# geiger-v2.net
KiCad netlist of a schematic drawn in EAGLE
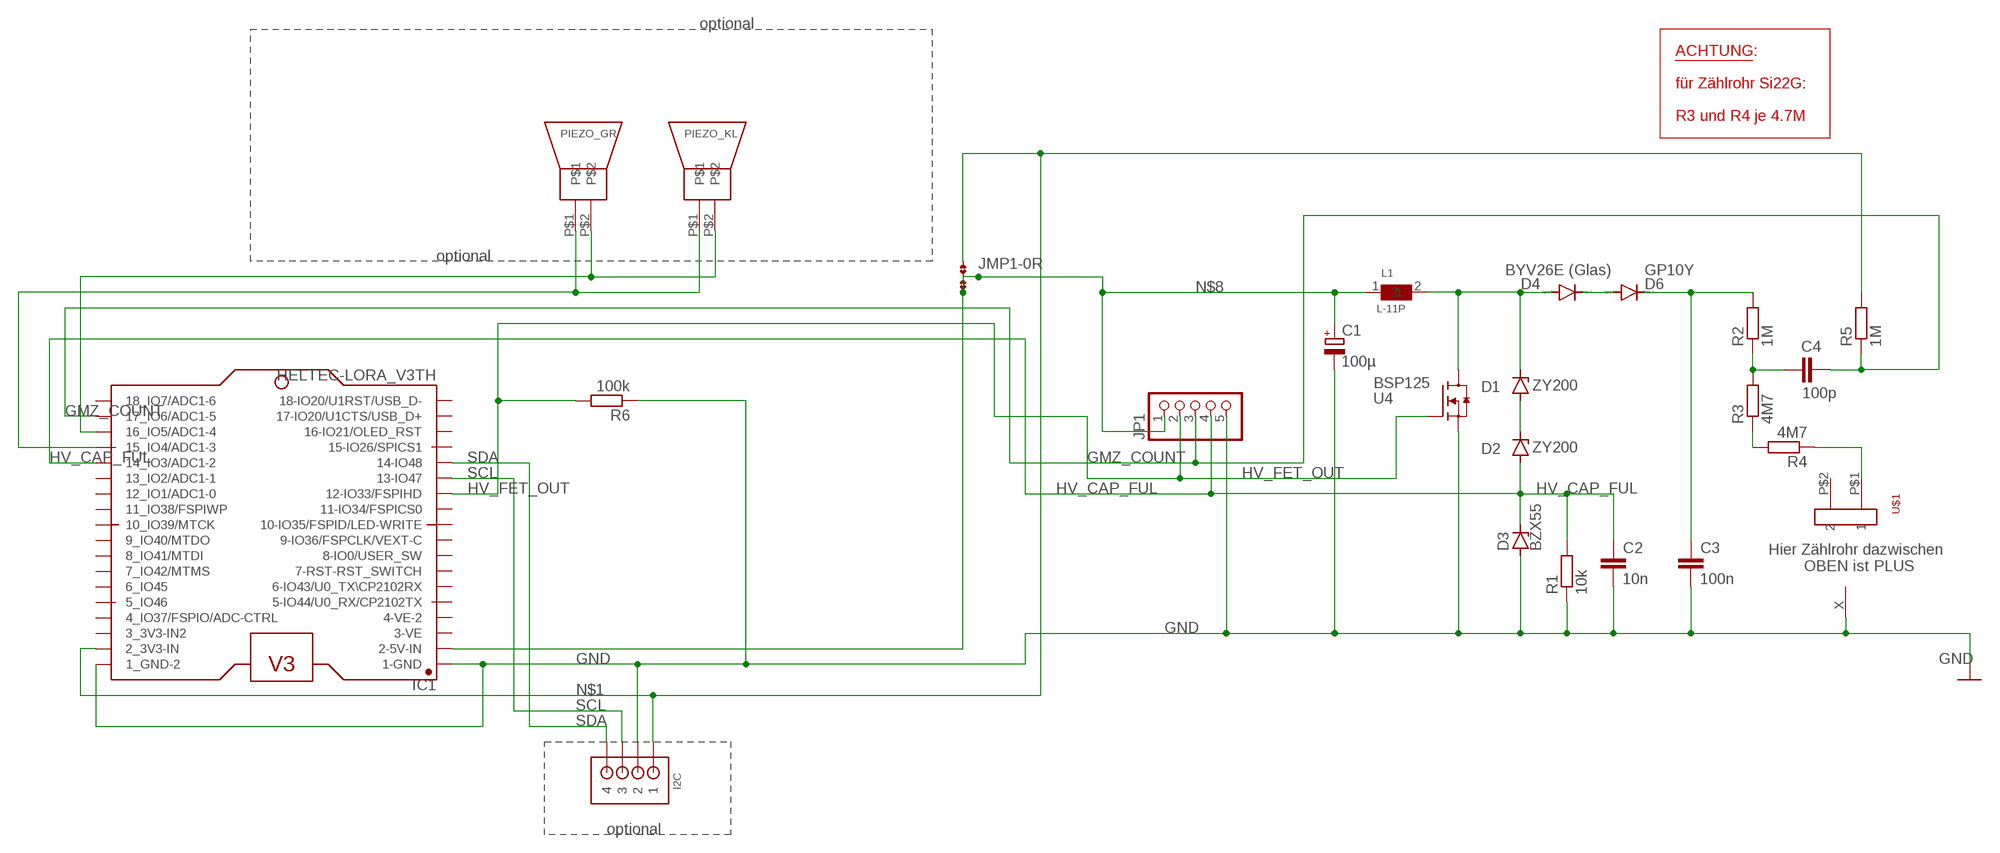
[diagram p0: schematic, sheet 1]

(export (version "E")
  (design (tool "Eeschema 10.0.6"))
  (components
    (comp (ref "C1")
      (value "100µ")
      (footprint "eagle-import:E2-5")
      (libsource (lib "eagle-import") (part "CPOL-EUE2-5"))
    )
    (comp (ref "C2")
      (value "10n")
      (footprint "eagle-import:C050-035X075")
      (libsource (lib "eagle-import") (part "C-EU050-035X075"))
    )
    (comp (ref "C3")
      (value "100n")
      (footprint "eagle-import:C150-072X183")
      (libsource (lib "eagle-import") (part "C-EU150-072X183"))
    )
    (comp (ref "C4")
      (value "100p")
      (footprint "eagle-import:C050-045X075")
      (libsource (lib "eagle-import") (part "C-EU050-045X075"))
    )
    (comp (ref "D1")
      (value "ZY200")
      (footprint "eagle-import:DO41Z10")
      (libsource (lib "eagle-import") (part "ZENER-DIODEDO41Z10"))
    )
    (comp (ref "D2")
      (value "ZY200")
      (footprint "eagle-import:DO41Z10")
      (libsource (lib "eagle-import") (part "ZENER-DIODEDO41Z10"))
    )
    (comp (ref "D3")
      (value "BZX55")
      (footprint "eagle-import:DO35Z10")
      (libsource (lib "eagle-import") (part "BZX55"))
    )
    (comp (ref "D4")
      (value "BYV26E (Glas)")
      (footprint "eagle-import:DO41-10")
      (libsource (lib "eagle-import") (part "1N4004"))
    )
    (comp (ref "D6")
      (value "GP10Y")
      (footprint "eagle-import:DO41-10")
      (libsource (lib "eagle-import") (part "1N4004"))
    )
    (comp (ref "I2C")
      (value "B4B-ZRSIDE_ENTRY")
      (footprint "eagle-import:S4B-ZR")
      (libsource (lib "eagle-import") (part "B4B-ZRSIDE_ENTRY"))
    )
    (comp (ref "IC1")
      (value "HELTEC-LORA_V3TH")
      (footprint "eagle-import:HELTEC_LORA_32")
      (libsource (lib "eagle-import") (part "HELTEC-LORA_V3TH"))
    )
    (comp (ref "JMP1")
      (value "0R-JUMPB")
      (footprint "eagle-import:B0R-JMP")
      (libsource (lib "eagle-import") (part "0R-JUMPB"))
    )
    (comp (ref "JP1")
      (value "PINHD-1X5")
      (footprint "eagle-import:1X05")
      (libsource (lib "eagle-import") (part "PINHD-1X5"))
    )
    (comp (ref "L1")
      (value "L-11P")
      (footprint "eagle-import:L-11P")
      (libsource (lib "eagle-import") (part "L-11P"))
    )
    (comp (ref "PIEZO_GR")
      (value "PIEPSER_BIG")
      (footprint "eagle-import:PIEPSER_BIG")
      (libsource (lib "eagle-import") (part "PIEPSER_BIG"))
    )
    (comp (ref "PIEZO_KL")
      (value "PIEPSER")
      (footprint "eagle-import:PIEPSER")
      (libsource (lib "eagle-import") (part "PIEPSER"))
    )
    (comp (ref "R1")
      (value "10k")
      (footprint "eagle-import:0207_10")
      (libsource (lib "eagle-import") (part "R-EU_0207/10"))
    )
    (comp (ref "R2")
      (value "1M")
      (footprint "eagle-import:0207_10")
      (libsource (lib "eagle-import") (part "R-EU_0207/10"))
    )
    (comp (ref "R3")
      (value "4M7")
      (footprint "eagle-import:0207_10")
      (libsource (lib "eagle-import") (part "R-EU_0207/10"))
    )
    (comp (ref "R4")
      (value "4M7")
      (footprint "eagle-import:0207_10")
      (libsource (lib "eagle-import") (part "R-EU_0207/10"))
    )
    (comp (ref "R5")
      (value "1M")
      (footprint "eagle-import:0207_10")
      (libsource (lib "eagle-import") (part "R-EU_0207/10"))
    )
    (comp (ref "R6")
      (value "100k")
      (footprint "eagle-import:0207_10")
      (libsource (lib "eagle-import") (part "R-EU_0207/10"))
    )
    (comp (ref "U$1")
      (value "FUSE_HOLDER")
      (footprint "eagle-import:FUSE_HOLDER")
      (libsource (lib "eagle-import") (part "FUSE_HOLDER"))
    )
    (comp (ref "U$5")
      (value "ONE_PAD")
      (footprint "eagle-import:ONE_PAD")
      (libsource (lib "eagle-import") (part "ONE_PAD"))
    )
    (comp (ref "U4")
      (value "BSP125")
      (footprint "eagle-import:SOT223")
      (libsource (lib "eagle-import") (part "BSP125"))
    )
  )
  (nets
    (net (code "1") (name "/3-VE") (class "Default")
      (node (ref "IC1") (pin "3-") (pinfunction "3-VE_3-") (pintype "power_in"))
    )
    (net (code "2") (name "/3_3V3-IN2") (class "Default")
      (node (ref "IC1") (pin "3_") (pinfunction "3_3V3-IN2_3_") (pintype "power_in"))
    )
    (net (code "3") (name "/4-VE-2") (class "Default")
      (node (ref "IC1") (pin "4-") (pinfunction "4-VE-2_4-") (pintype "power_in"))
    )
    (net (code "4") (name "/GMZ_COUNT") (class "Default")
      (node (ref "C4") (pin "2") (pinfunction "2_2") (pintype "passive"))
      (node (ref "IC1") (pin "17_") (pinfunction "17_IO6/ADC1-5_17_") (pintype "bidirectional"))
      (node (ref "JP1") (pin "3") (pinfunction "3_3") (pintype "passive"))
      (node (ref "R5") (pin "1") (pinfunction "1_1") (pintype "passive"))
    )
    (net (code "5") (name "/HV_CAP_FUL") (class "Default")
      (node (ref "C2") (pin "1") (pinfunction "1_1") (pintype "passive"))
      (node (ref "D2") (pin "A") (pinfunction "A_A") (pintype "passive"))
      (node (ref "D3") (pin "C") (pinfunction "C_C") (pintype "passive"))
      (node (ref "IC1") (pin "14_") (pinfunction "14_IO3/ADC1-2_14_") (pintype "bidirectional"))
      (node (ref "JP1") (pin "4") (pinfunction "4_4") (pintype "passive"))
      (node (ref "R1") (pin "2") (pinfunction "2_2") (pintype "passive"))
    )
    (net (code "6") (name "/HV_FET_OUT") (class "Default")
      (node (ref "IC1") (pin "12-") (pinfunction "12-IO33/FSPIHD_12-") (pintype "bidirectional"))
      (node (ref "JP1") (pin "2") (pinfunction "2_2") (pintype "passive"))
      (node (ref "R6") (pin "2") (pinfunction "2_2") (pintype "passive"))
      (node (ref "U4") (pin "1") (pinfunction "G_1") (pintype "passive"))
    )
    (net (code "7") (name "/N$1") (class "Default")
      (node (ref "I2C") (pin "1") (pinfunction "1_1") (pintype "bidirectional"))
      (node (ref "IC1") (pin "2_") (pinfunction "2_3V3-IN_2_") (pintype "power_in"))
      (node (ref "JMP1") (pin "1") (pinfunction "1_1") (pintype "passive"))
      (node (ref "R5") (pin "2") (pinfunction "2_2") (pintype "passive"))
    )
    (net (code "8") (name "/N$8") (class "Default")
      (node (ref "C1") (pin "+") (pinfunction "+_+") (pintype "passive"))
      (node (ref "IC1") (pin "2-") (pinfunction "2-5V-IN_2-") (pintype "power_in"))
      (node (ref "JMP1") (pin "2") (pinfunction "2_2") (pintype "passive"))
      (node (ref "JMP1") (pin "3") (pinfunction "3_3") (pintype "passive"))
      (node (ref "JP1") (pin "1") (pinfunction "1_1") (pintype "passive"))
      (node (ref "L1") (pin "1") (pinfunction "1_1") (pintype "bidirectional"))
    )
    (net (code "9") (name "/SCL") (class "Default")
      (node (ref "I2C") (pin "3") (pinfunction "3_3") (pintype "bidirectional"))
      (node (ref "IC1") (pin "13-") (pinfunction "13-IO47_13-") (pintype "bidirectional"))
    )
    (net (code "10") (name "/SDA") (class "Default")
      (node (ref "I2C") (pin "4") (pinfunction "4_4") (pintype "bidirectional"))
      (node (ref "IC1") (pin "14-") (pinfunction "14-IO48_14-") (pintype "bidirectional"))
    )
    (net (code "11") (name "GND") (class "Default")
      (node (ref "C1") (pin "-") (pinfunction "-_-") (pintype "passive"))
      (node (ref "C2") (pin "2") (pinfunction "2_2") (pintype "passive"))
      (node (ref "C3") (pin "2") (pinfunction "2_2") (pintype "passive"))
      (node (ref "D3") (pin "A") (pinfunction "A_A") (pintype "passive"))
      (node (ref "I2C") (pin "2") (pinfunction "2_2") (pintype "bidirectional"))
      (node (ref "IC1") (pin "1-") (pinfunction "1-GND_1-") (pintype "power_in"))
      (node (ref "IC1") (pin "1_") (pinfunction "1_GND-2_1_") (pintype "power_in"))
      (node (ref "JP1") (pin "5") (pinfunction "5_5") (pintype "passive"))
      (node (ref "R1") (pin "1") (pinfunction "1_1") (pintype "passive"))
      (node (ref "R6") (pin "1") (pinfunction "1_1") (pintype "passive"))
      (node (ref "U$5") (pin "X") (pinfunction "P$1_X") (pintype "bidirectional"))
      (node (ref "U4") (pin "3") (pinfunction "S_3") (pintype "passive"))
    )
    (net (code "12") (name "Net-(C3-Pad1)") (class "Default")
      (node (ref "C3") (pin "1") (pinfunction "1_1") (pintype "passive"))
      (node (ref "D6") (pin "C") (pinfunction "C_C") (pintype "passive"))
      (node (ref "R2") (pin "2") (pinfunction "2_2") (pintype "passive"))
    )
    (net (code "13") (name "Net-(C4-Pad1)") (class "Default")
      (node (ref "C4") (pin "1") (pinfunction "1_1") (pintype "passive"))
      (node (ref "R2") (pin "1") (pinfunction "1_1") (pintype "passive"))
      (node (ref "R3") (pin "2") (pinfunction "2_2") (pintype "passive"))
    )
    (net (code "14") (name "Net-(D1-PadA)") (class "Default")
      (node (ref "D1") (pin "A") (pinfunction "A_A") (pintype "passive"))
      (node (ref "D2") (pin "C") (pinfunction "C_C") (pintype "passive"))
    )
    (net (code "15") (name "Net-(D1-PadC)") (class "Default")
      (node (ref "D1") (pin "C") (pinfunction "C_C") (pintype "passive"))
      (node (ref "D4") (pin "A") (pinfunction "A_A") (pintype "passive"))
      (node (ref "L1") (pin "2") (pinfunction "2_2") (pintype "bidirectional"))
      (node (ref "U4") (pin "2") (pinfunction "D_2") (pintype "passive"))
      (node (ref "U4") (pin "4") (pinfunction "D_4") (pintype "passive"))
    )
    (net (code "16") (name "Net-(D4-PadC)") (class "Default")
      (node (ref "D4") (pin "C") (pinfunction "C_C") (pintype "passive"))
      (node (ref "D6") (pin "A") (pinfunction "A_A") (pintype "passive"))
    )
    (net (code "17") (name "Net-(IC1-15_IO4{slash}ADC1-3)") (class "Default")
      (node (ref "IC1") (pin "15_") (pinfunction "15_IO4/ADC1-3_15_") (pintype "bidirectional"))
      (node (ref "PIEZO_GR") (pin "P$1") (pinfunction "P$1_P$1") (pintype "bidirectional"))
      (node (ref "PIEZO_KL") (pin "P$1") (pinfunction "P$1_P$1") (pintype "bidirectional"))
    )
    (net (code "18") (name "Net-(IC1-16_IO5{slash}ADC1-4)") (class "Default")
      (node (ref "IC1") (pin "16_") (pinfunction "16_IO5/ADC1-4_16_") (pintype "bidirectional"))
      (node (ref "PIEZO_GR") (pin "P$2") (pinfunction "P$2_P$2") (pintype "bidirectional"))
      (node (ref "PIEZO_KL") (pin "P$2") (pinfunction "P$2_P$2") (pintype "bidirectional"))
    )
    (net (code "19") (name "Net-(R3-Pad1)") (class "Default")
      (node (ref "R3") (pin "1") (pinfunction "1_1") (pintype "passive"))
      (node (ref "R4") (pin "2") (pinfunction "2_2") (pintype "passive"))
    )
    (net (code "20") (name "Net-(U$1-1)") (class "Default")
      (node (ref "R4") (pin "1") (pinfunction "1_1") (pintype "passive"))
      (node (ref "U$1") (pin "P$1") (pinfunction "1_P$1") (pintype "bidirectional"))
    )
    (net (code "21") (name "unconnected-(IC1-4_IO37{slash}FSPIO{slash}ADC-CTRL-Pad4_)") (class "Default")
      (node (ref "IC1") (pin "4_") (pinfunction "4_IO37/FSPIO/ADC-CTRL_4_") (pintype "input"))
    )
    (net (code "22") (name "unconnected-(IC1-5-IO44{slash}U0_RX{slash}CP2102TX-Pad5-)") (class "Default")
      (node (ref "IC1") (pin "5-") (pinfunction "5-IO44/U0_RX/CP2102TX_5-") (pintype "bidirectional"))
    )
    (net (code "23") (name "unconnected-(IC1-5_IO46-Pad5_)") (class "Default")
      (node (ref "IC1") (pin "5_") (pinfunction "5_IO46_5_") (pintype "input"))
    )
    (net (code "24") (name "unconnected-(IC1-6-IO43{slash}U0_TX\\CP2102RX-Pad6-)") (class "Default")
      (node (ref "IC1") (pin "6-") (pinfunction "6-IO43/U0_TX\\CP2102RX_6-") (pintype "bidirectional"))
    )
    (net (code "25") (name "unconnected-(IC1-6_IO45-Pad6_)") (class "Default")
      (node (ref "IC1") (pin "6_") (pinfunction "6_IO45_6_") (pintype "input"))
    )
    (net (code "26") (name "unconnected-(IC1-7-RST-RST_SWITCH-Pad7-)") (class "Default")
      (node (ref "IC1") (pin "7-") (pinfunction "7-RST-RST_SWITCH_7-") (pintype "bidirectional"))
    )
    (net (code "27") (name "unconnected-(IC1-7_IO42{slash}MTMS-Pad7_)") (class "Default")
      (node (ref "IC1") (pin "7_") (pinfunction "7_IO42/MTMS_7_") (pintype "input"))
    )
    (net (code "28") (name "unconnected-(IC1-8-IO0{slash}USER_SW-Pad8-)") (class "Default")
      (node (ref "IC1") (pin "8-") (pinfunction "8-IO0/USER_SW_8-") (pintype "bidirectional"))
    )
    (net (code "29") (name "unconnected-(IC1-8_IO41{slash}MTDI-Pad8_)") (class "Default")
      (node (ref "IC1") (pin "8_") (pinfunction "8_IO41/MTDI_8_") (pintype "input"))
    )
    (net (code "30") (name "unconnected-(IC1-9-IO36{slash}FSPCLK{slash}VEXT-C-Pad9-)") (class "Default")
      (node (ref "IC1") (pin "9-") (pinfunction "9-IO36/FSPCLK/VEXT-C_9-") (pintype "bidirectional"))
    )
    (net (code "31") (name "unconnected-(IC1-9_IO40{slash}MTDO-Pad9_)") (class "Default")
      (node (ref "IC1") (pin "9_") (pinfunction "9_IO40/MTDO_9_") (pintype "input"))
    )
    (net (code "32") (name "unconnected-(IC1-10-IO35{slash}FSPID{slash}LED-WRITE-Pad10-)") (class "Default")
      (node (ref "IC1") (pin "10-") (pinfunction "10-IO35/FSPID/LED-WRITE_10-") (pintype "bidirectional"))
    )
    (net (code "33") (name "unconnected-(IC1-10_IO39{slash}MTCK-Pad10_)") (class "Default")
      (node (ref "IC1") (pin "10_") (pinfunction "10_IO39/MTCK_10_") (pintype "bidirectional"))
    )
    (net (code "34") (name "unconnected-(IC1-11-IO34{slash}FSPICS0-Pad11.)") (class "Default")
      (node (ref "IC1") (pin "11.") (pinfunction "11-IO34/FSPICS0_11.") (pintype "bidirectional"))
    )
    (net (code "35") (name "unconnected-(IC1-11_IO38{slash}FSPIWP-Pad11_)") (class "Default")
      (node (ref "IC1") (pin "11_") (pinfunction "11_IO38/FSPIWP_11_") (pintype "bidirectional"))
    )
    (net (code "36") (name "unconnected-(IC1-12_IO1{slash}ADC1-0-Pad12_)") (class "Default")
      (node (ref "IC1") (pin "12_") (pinfunction "12_IO1/ADC1-0_12_") (pintype "bidirectional"))
    )
    (net (code "37") (name "unconnected-(IC1-13_IO2{slash}ADC1-1-Pad13_)") (class "Default")
      (node (ref "IC1") (pin "13_") (pinfunction "13_IO2/ADC1-1_13_") (pintype "bidirectional"))
    )
    (net (code "38") (name "unconnected-(IC1-15-IO26{slash}SPICS1-Pad15-)") (class "Default")
      (node (ref "IC1") (pin "15-") (pinfunction "15-IO26/SPICS1_15-") (pintype "bidirectional"))
    )
    (net (code "39") (name "unconnected-(IC1-16-IO21{slash}OLED_RST-Pad16-)") (class "Default")
      (node (ref "IC1") (pin "16-") (pinfunction "16-IO21/OLED_RST_16-") (pintype "bidirectional"))
    )
    (net (code "40") (name "unconnected-(IC1-17-IO20{slash}U1CTS{slash}USB_D+-Pad17-)") (class "Default")
      (node (ref "IC1") (pin "17-") (pinfunction "17-IO20/U1CTS/USB_D+_17-") (pintype "bidirectional"))
    )
    (net (code "41") (name "unconnected-(IC1-18-IO20{slash}U1RST{slash}USB_D--Pad18-)") (class "Default")
      (node (ref "IC1") (pin "18-") (pinfunction "18-IO20/U1RST/USB_D-_18-") (pintype "bidirectional"))
    )
    (net (code "42") (name "unconnected-(IC1-18_IO7{slash}ADC1-6-Pad18_)") (class "Default")
      (node (ref "IC1") (pin "18_") (pinfunction "18_IO7/ADC1-6_18_") (pintype "bidirectional"))
    )
    (net (code "43") (name "unconnected-(U$1-2-PadP$2)") (class "Default")
      (node (ref "U$1") (pin "P$2") (pinfunction "2_P$2") (pintype "bidirectional"))
    )
  )
)
